# Compute_Module_POWER.net
KiCad netlist of a schematic drawn in Altium Designer
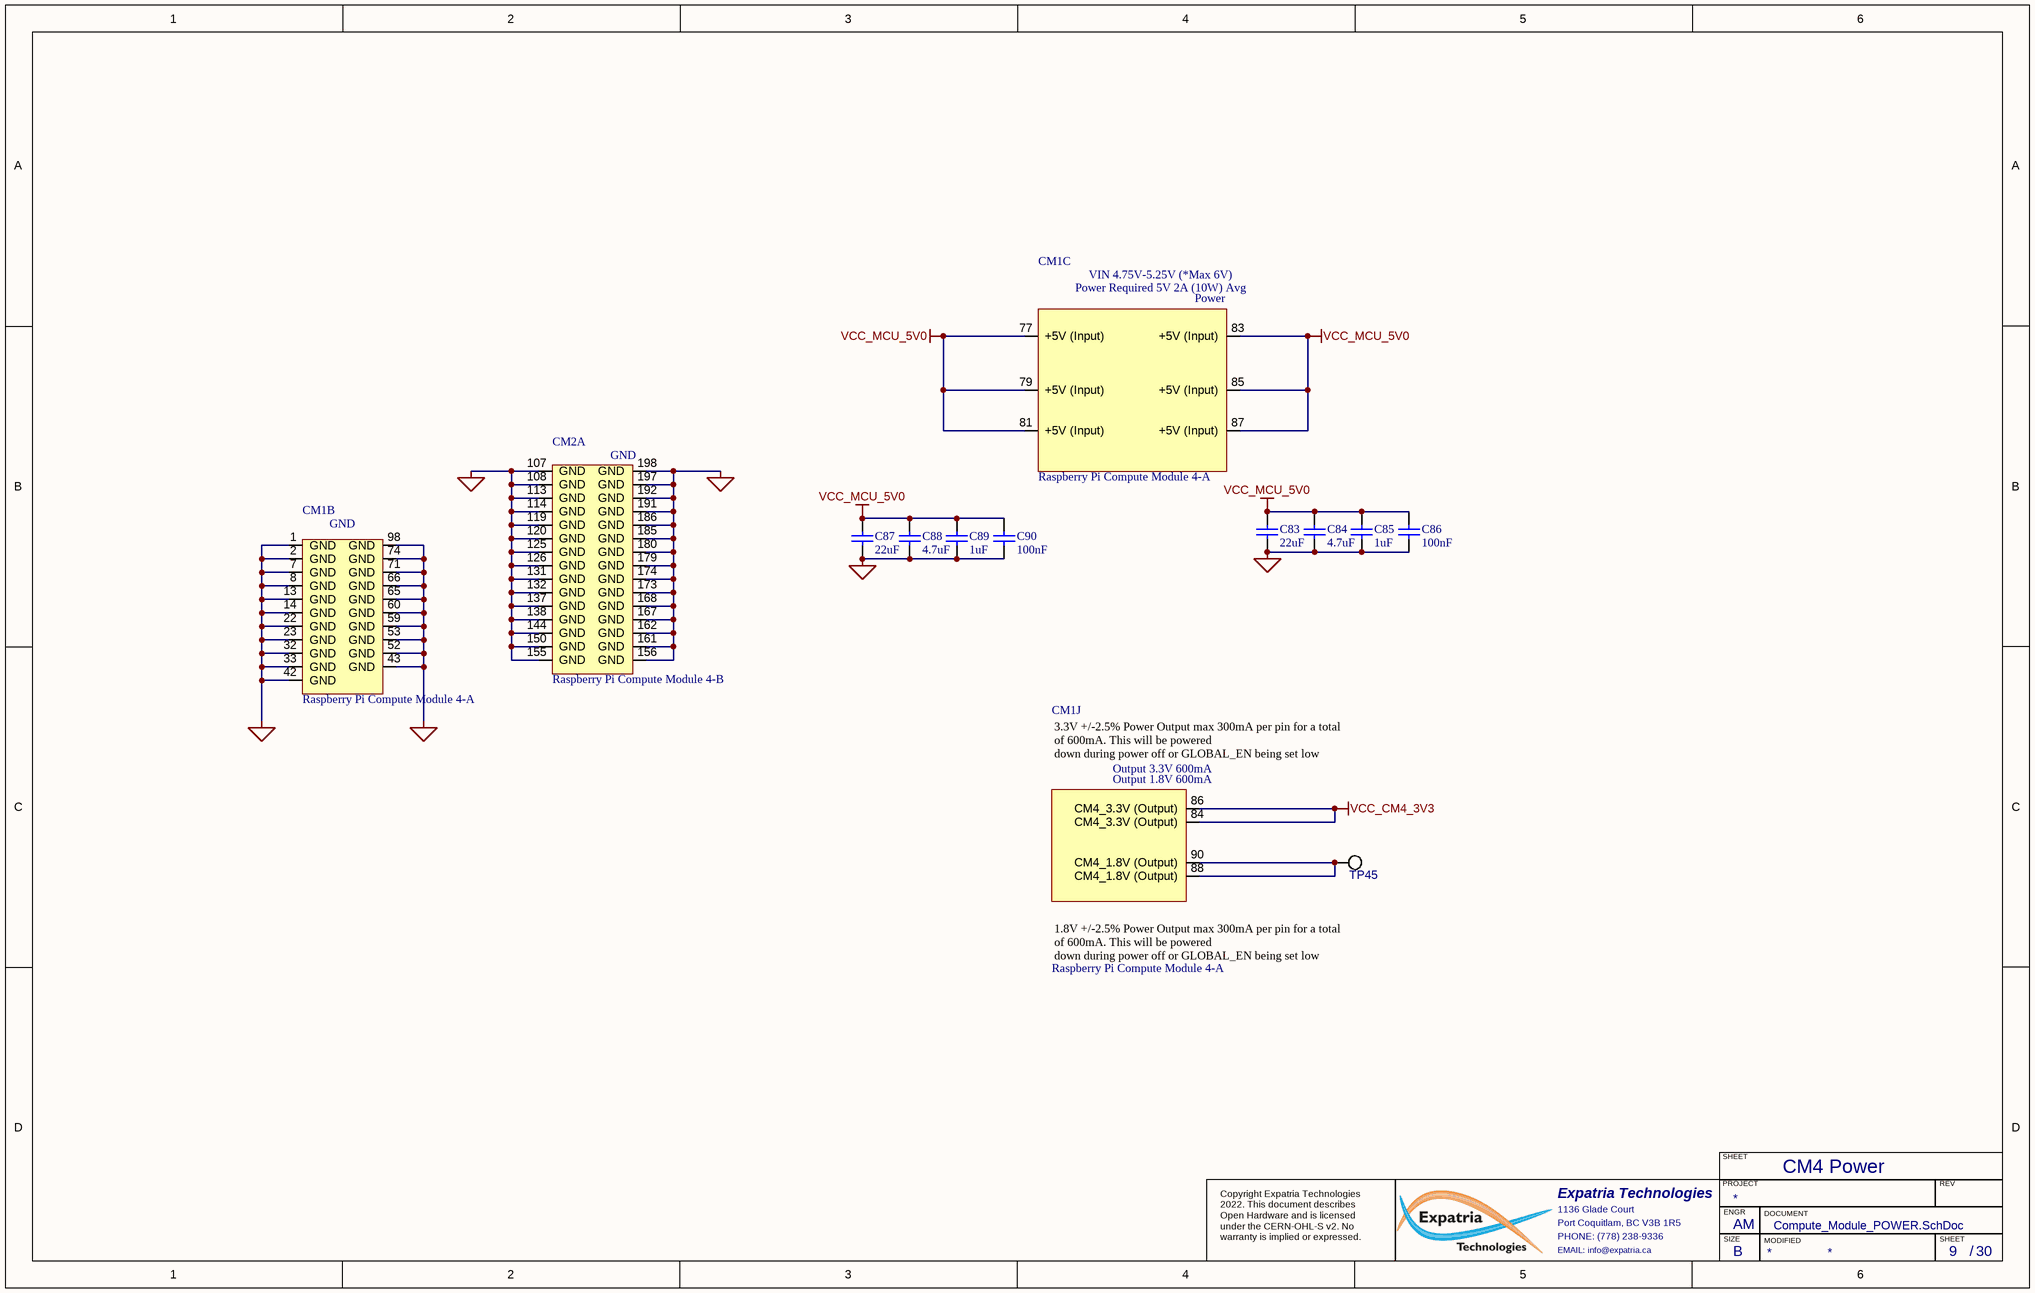
[diagram p0: Compute_Module_POWER.SchDoc]

(export (version "E")
  (design (tool "Eeschema 10.0.6"))
  (components
    (comp (ref "C83")
      (value "22uF")
      (footprint "0805_C")
      (description "Chip capacitors")
      (fields
        (field (name "MANUFACTURER") "Samsung Electro-Mechanics")
        (field (name "PARTNUMBER") "CL21A226MAQNNNE")
      )
      (libsource (lib "Cap") (part "0805 22uF (226) 20% 25V"))
    )
    (comp (ref "C84")
      (value "4.7uF")
      (footprint "0603_C")
      (description "Chip capacitors")
      (fields
        (field (name "MANUFACTURER") "Samsung Electro-Mechanics")
        (field (name "PARTNUMBER") "CL10A475KO8NNNC")
      )
      (libsource (lib "Cap") (part "0603 4.7uF (475) 10% 16V"))
    )
    (comp (ref "C85")
      (value "1uF")
      (footprint "0603_C")
      (description "Chip capacitors")
      (fields
        (field (name "MANUFACTURER") "Samsung Electro-Mechanics")
        (field (name "MANUFACTURER PART NUMBER") "CL10A105KB8NNNC")
      )
      (libsource (lib "Cap") (part "0603 1uF (105) 10% 50V"))
    )
    (comp (ref "C86")
      (value "100nF")
      (footprint "0603_C")
      (description "Chip capacitors")
      (fields
        (field (name "MANUFACTURER") "YAGEO")
        (field (name "MANUFACTURER PART NUMBER") "CC0603KRX7R9BB104")
      )
      (libsource (lib "Cap") (part "0603 100nF (104) 10% 50V"))
    )
    (comp (ref "C87")
      (value "22uF")
      (footprint "0805_C")
      (description "Chip capacitors")
      (fields
        (field (name "MANUFACTURER") "Samsung Electro-Mechanics")
        (field (name "PARTNUMBER") "CL21A226MAQNNNE")
      )
      (libsource (lib "Cap") (part "0805 22uF (226) 20% 25V"))
    )
    (comp (ref "C88")
      (value "4.7uF")
      (footprint "0603_C")
      (description "Chip capacitors")
      (fields
        (field (name "MANUFACTURER") "Samsung Electro-Mechanics")
        (field (name "PARTNUMBER") "CL10A475KO8NNNC")
      )
      (libsource (lib "Cap") (part "0603 4.7uF (475) 10% 16V"))
    )
    (comp (ref "C89")
      (value "1uF")
      (footprint "0603_C")
      (description "Chip capacitors")
      (fields
        (field (name "MANUFACTURER") "Samsung Electro-Mechanics")
        (field (name "MANUFACTURER PART NUMBER") "CL10A105KB8NNNC")
      )
      (libsource (lib "Cap") (part "0603 1uF (105) 10% 50V"))
    )
    (comp (ref "C90")
      (value "100nF")
      (footprint "0603_C")
      (description "Chip capacitors")
      (fields
        (field (name "MANUFACTURER") "YAGEO")
        (field (name "MANUFACTURER PART NUMBER") "CC0603KRX7R9BB104")
      )
      (libsource (lib "Cap") (part "0603 100nF (104) 10% 50V"))
    )
    (comp (ref "CM1")
      (value "Raspberry Pi Compute Module 4-A")
      (footprint "DF40HC30100DS04V51")
      (description "Raspberry Pi Compute Module 4 Pins 1-100 (Connector A)")
      (fields
        (field (name "MANUFACTURER") "Hirose")
        (field (name "MANUFACTURER PART NUMBER") "DF40HC(3.0)-100DS-0.4V(51)")
      )
      (libsource (lib "Sienci_Labs") (part "CM4_Module_A"))
    )
    (comp (ref "CM2")
      (value "Raspberry Pi Compute Module 4-B")
      (footprint "DF40HC30100DS04V51 - p101-200")
      (description "Raspberry Pi Compute Module 4 Pins 101-200 (Connector B)")
      (fields
        (field (name "MANUFACTURER") "Hirose")
        (field (name "MANUFACTURER PART NUMBER") "DF40HC(3.0)-100DS-0.4V(51)")
      )
      (libsource (lib "Sienci_Labs") (part "CM4_Module_B"))
    )
    (comp (ref "TP45")
      (value "TESTPOINT")
      (footprint "TP/SMALL")
      (description "Test Point")
      (libsource (lib "Sienci_Labs") (part "TESTPOINT"))
    )
  )
  (nets
    (net (code "1") (name "MCU_GND") (class "Default")
      (node (ref "C83") (pin "1") (pinfunction "1_1") (pintype "passive"))
      (node (ref "C84") (pin "1") (pinfunction "1_1") (pintype "passive"))
      (node (ref "C85") (pin "1") (pinfunction "1_1") (pintype "passive"))
      (node (ref "C86") (pin "1") (pinfunction "1_1") (pintype "passive"))
      (node (ref "C87") (pin "1") (pinfunction "1_1") (pintype "passive"))
      (node (ref "C88") (pin "1") (pinfunction "1_1") (pintype "passive"))
      (node (ref "C89") (pin "1") (pinfunction "1_1") (pintype "passive"))
      (node (ref "C90") (pin "1") (pinfunction "1_1") (pintype "passive"))
      (node (ref "CM1") (pin "1") (pinfunction "GND_1") (pintype "power_in"))
      (node (ref "CM1") (pin "13") (pinfunction "GND_13") (pintype "power_in"))
      (node (ref "CM1") (pin "14") (pinfunction "GND_14") (pintype "power_in"))
      (node (ref "CM1") (pin "2") (pinfunction "GND_2") (pintype "power_in"))
      (node (ref "CM1") (pin "22") (pinfunction "GND_22") (pintype "power_in"))
      (node (ref "CM1") (pin "23") (pinfunction "GND_23") (pintype "power_in"))
      (node (ref "CM1") (pin "32") (pinfunction "GND_32") (pintype "power_in"))
      (node (ref "CM1") (pin "33") (pinfunction "GND_33") (pintype "power_in"))
      (node (ref "CM1") (pin "42") (pinfunction "GND_42") (pintype "power_in"))
      (node (ref "CM1") (pin "43") (pinfunction "GND_43") (pintype "power_in"))
      (node (ref "CM1") (pin "52") (pinfunction "GND_52") (pintype "power_in"))
      (node (ref "CM1") (pin "53") (pinfunction "GND_53") (pintype "power_in"))
      (node (ref "CM1") (pin "59") (pinfunction "GND_59") (pintype "power_in"))
      (node (ref "CM1") (pin "60") (pinfunction "GND_60") (pintype "power_in"))
      (node (ref "CM1") (pin "65") (pinfunction "GND_65") (pintype "power_in"))
      (node (ref "CM1") (pin "66") (pinfunction "GND_66") (pintype "power_in"))
      (node (ref "CM1") (pin "7") (pinfunction "GND_7") (pintype "power_in"))
      (node (ref "CM1") (pin "71") (pinfunction "GND_71") (pintype "power_in"))
      (node (ref "CM1") (pin "74") (pinfunction "GND_74") (pintype "power_in"))
      (node (ref "CM1") (pin "8") (pinfunction "GND_8") (pintype "power_in"))
      (node (ref "CM1") (pin "98") (pinfunction "GND_98") (pintype "power_in"))
      (node (ref "CM2") (pin "107") (pinfunction "GND_107") (pintype "power_in"))
      (node (ref "CM2") (pin "108") (pinfunction "GND_108") (pintype "power_in"))
      (node (ref "CM2") (pin "113") (pinfunction "GND_113") (pintype "power_in"))
      (node (ref "CM2") (pin "114") (pinfunction "GND_114") (pintype "power_in"))
      (node (ref "CM2") (pin "119") (pinfunction "GND_119") (pintype "power_in"))
      (node (ref "CM2") (pin "120") (pinfunction "GND_120") (pintype "power_in"))
      (node (ref "CM2") (pin "125") (pinfunction "GND_125") (pintype "power_in"))
      (node (ref "CM2") (pin "126") (pinfunction "GND_126") (pintype "power_in"))
      (node (ref "CM2") (pin "131") (pinfunction "GND_131") (pintype "power_in"))
      (node (ref "CM2") (pin "132") (pinfunction "GND_132") (pintype "power_in"))
      (node (ref "CM2") (pin "137") (pinfunction "GND_137") (pintype "power_in"))
      (node (ref "CM2") (pin "138") (pinfunction "GND_138") (pintype "power_in"))
      (node (ref "CM2") (pin "144") (pinfunction "GND_144") (pintype "power_in"))
      (node (ref "CM2") (pin "150") (pinfunction "GND_150") (pintype "power_in"))
      (node (ref "CM2") (pin "155") (pinfunction "GND_155") (pintype "power_in"))
      (node (ref "CM2") (pin "156") (pinfunction "GND_156") (pintype "power_in"))
      (node (ref "CM2") (pin "161") (pinfunction "GND_161") (pintype "power_in"))
      (node (ref "CM2") (pin "162") (pinfunction "GND_162") (pintype "power_in"))
      (node (ref "CM2") (pin "167") (pinfunction "GND_167") (pintype "power_in"))
      (node (ref "CM2") (pin "168") (pinfunction "GND_168") (pintype "power_in"))
      (node (ref "CM2") (pin "173") (pinfunction "GND_173") (pintype "power_in"))
      (node (ref "CM2") (pin "174") (pinfunction "GND_174") (pintype "power_in"))
      (node (ref "CM2") (pin "179") (pinfunction "GND_179") (pintype "power_in"))
      (node (ref "CM2") (pin "180") (pinfunction "GND_180") (pintype "power_in"))
      (node (ref "CM2") (pin "185") (pinfunction "GND_185") (pintype "power_in"))
      (node (ref "CM2") (pin "186") (pinfunction "GND_186") (pintype "power_in"))
      (node (ref "CM2") (pin "191") (pinfunction "GND_191") (pintype "power_in"))
      (node (ref "CM2") (pin "192") (pinfunction "GND_192") (pintype "power_in"))
      (node (ref "CM2") (pin "197") (pinfunction "GND_197") (pintype "power_in"))
      (node (ref "CM2") (pin "198") (pinfunction "GND_198") (pintype "power_in"))
    )
    (net (code "2") (name "Net-(CM1J-CM4_1.8V_(Output)-Pad88)") (class "Default")
      (node (ref "CM1") (pin "88") (pinfunction "CM4_1.8V_(Output)_88") (pintype "power_in"))
      (node (ref "CM1") (pin "90") (pinfunction "CM4_1.8V_(Output)_90") (pintype "power_in"))
      (node (ref "TP45") (pin "1") (pintype "passive"))
    )
    (net (code "3") (name "VCC_CM4_3V3") (class "Default")
      (node (ref "CM1") (pin "84") (pinfunction "CM4_3.3V_(Output)_84") (pintype "power_in"))
      (node (ref "CM1") (pin "86") (pinfunction "CM4_3.3V_(Output)_86") (pintype "power_in"))
    )
    (net (code "4") (name "VCC_MCU_5V0") (class "Default")
      (node (ref "C83") (pin "2") (pinfunction "2_2") (pintype "passive"))
      (node (ref "C84") (pin "2") (pinfunction "2_2") (pintype "passive"))
      (node (ref "C85") (pin "2") (pinfunction "2_2") (pintype "passive"))
      (node (ref "C86") (pin "2") (pinfunction "2_2") (pintype "passive"))
      (node (ref "C87") (pin "2") (pinfunction "2_2") (pintype "passive"))
      (node (ref "C88") (pin "2") (pinfunction "2_2") (pintype "passive"))
      (node (ref "C89") (pin "2") (pinfunction "2_2") (pintype "passive"))
      (node (ref "C90") (pin "2") (pinfunction "2_2") (pintype "passive"))
      (node (ref "CM1") (pin "77") (pinfunction "+5V_(Input)_77") (pintype "power_in"))
      (node (ref "CM1") (pin "79") (pinfunction "+5V_(Input)_79") (pintype "power_in"))
      (node (ref "CM1") (pin "81") (pinfunction "+5V_(Input)_81") (pintype "power_in"))
      (node (ref "CM1") (pin "83") (pinfunction "+5V_(Input)_83") (pintype "power_in"))
      (node (ref "CM1") (pin "85") (pinfunction "+5V_(Input)_85") (pintype "power_in"))
      (node (ref "CM1") (pin "87") (pinfunction "+5V_(Input)_87") (pintype "power_in"))
    )
  )
)
